# LightLink_V2.net
KiCad netlist of a schematic drawn in Altium Designer
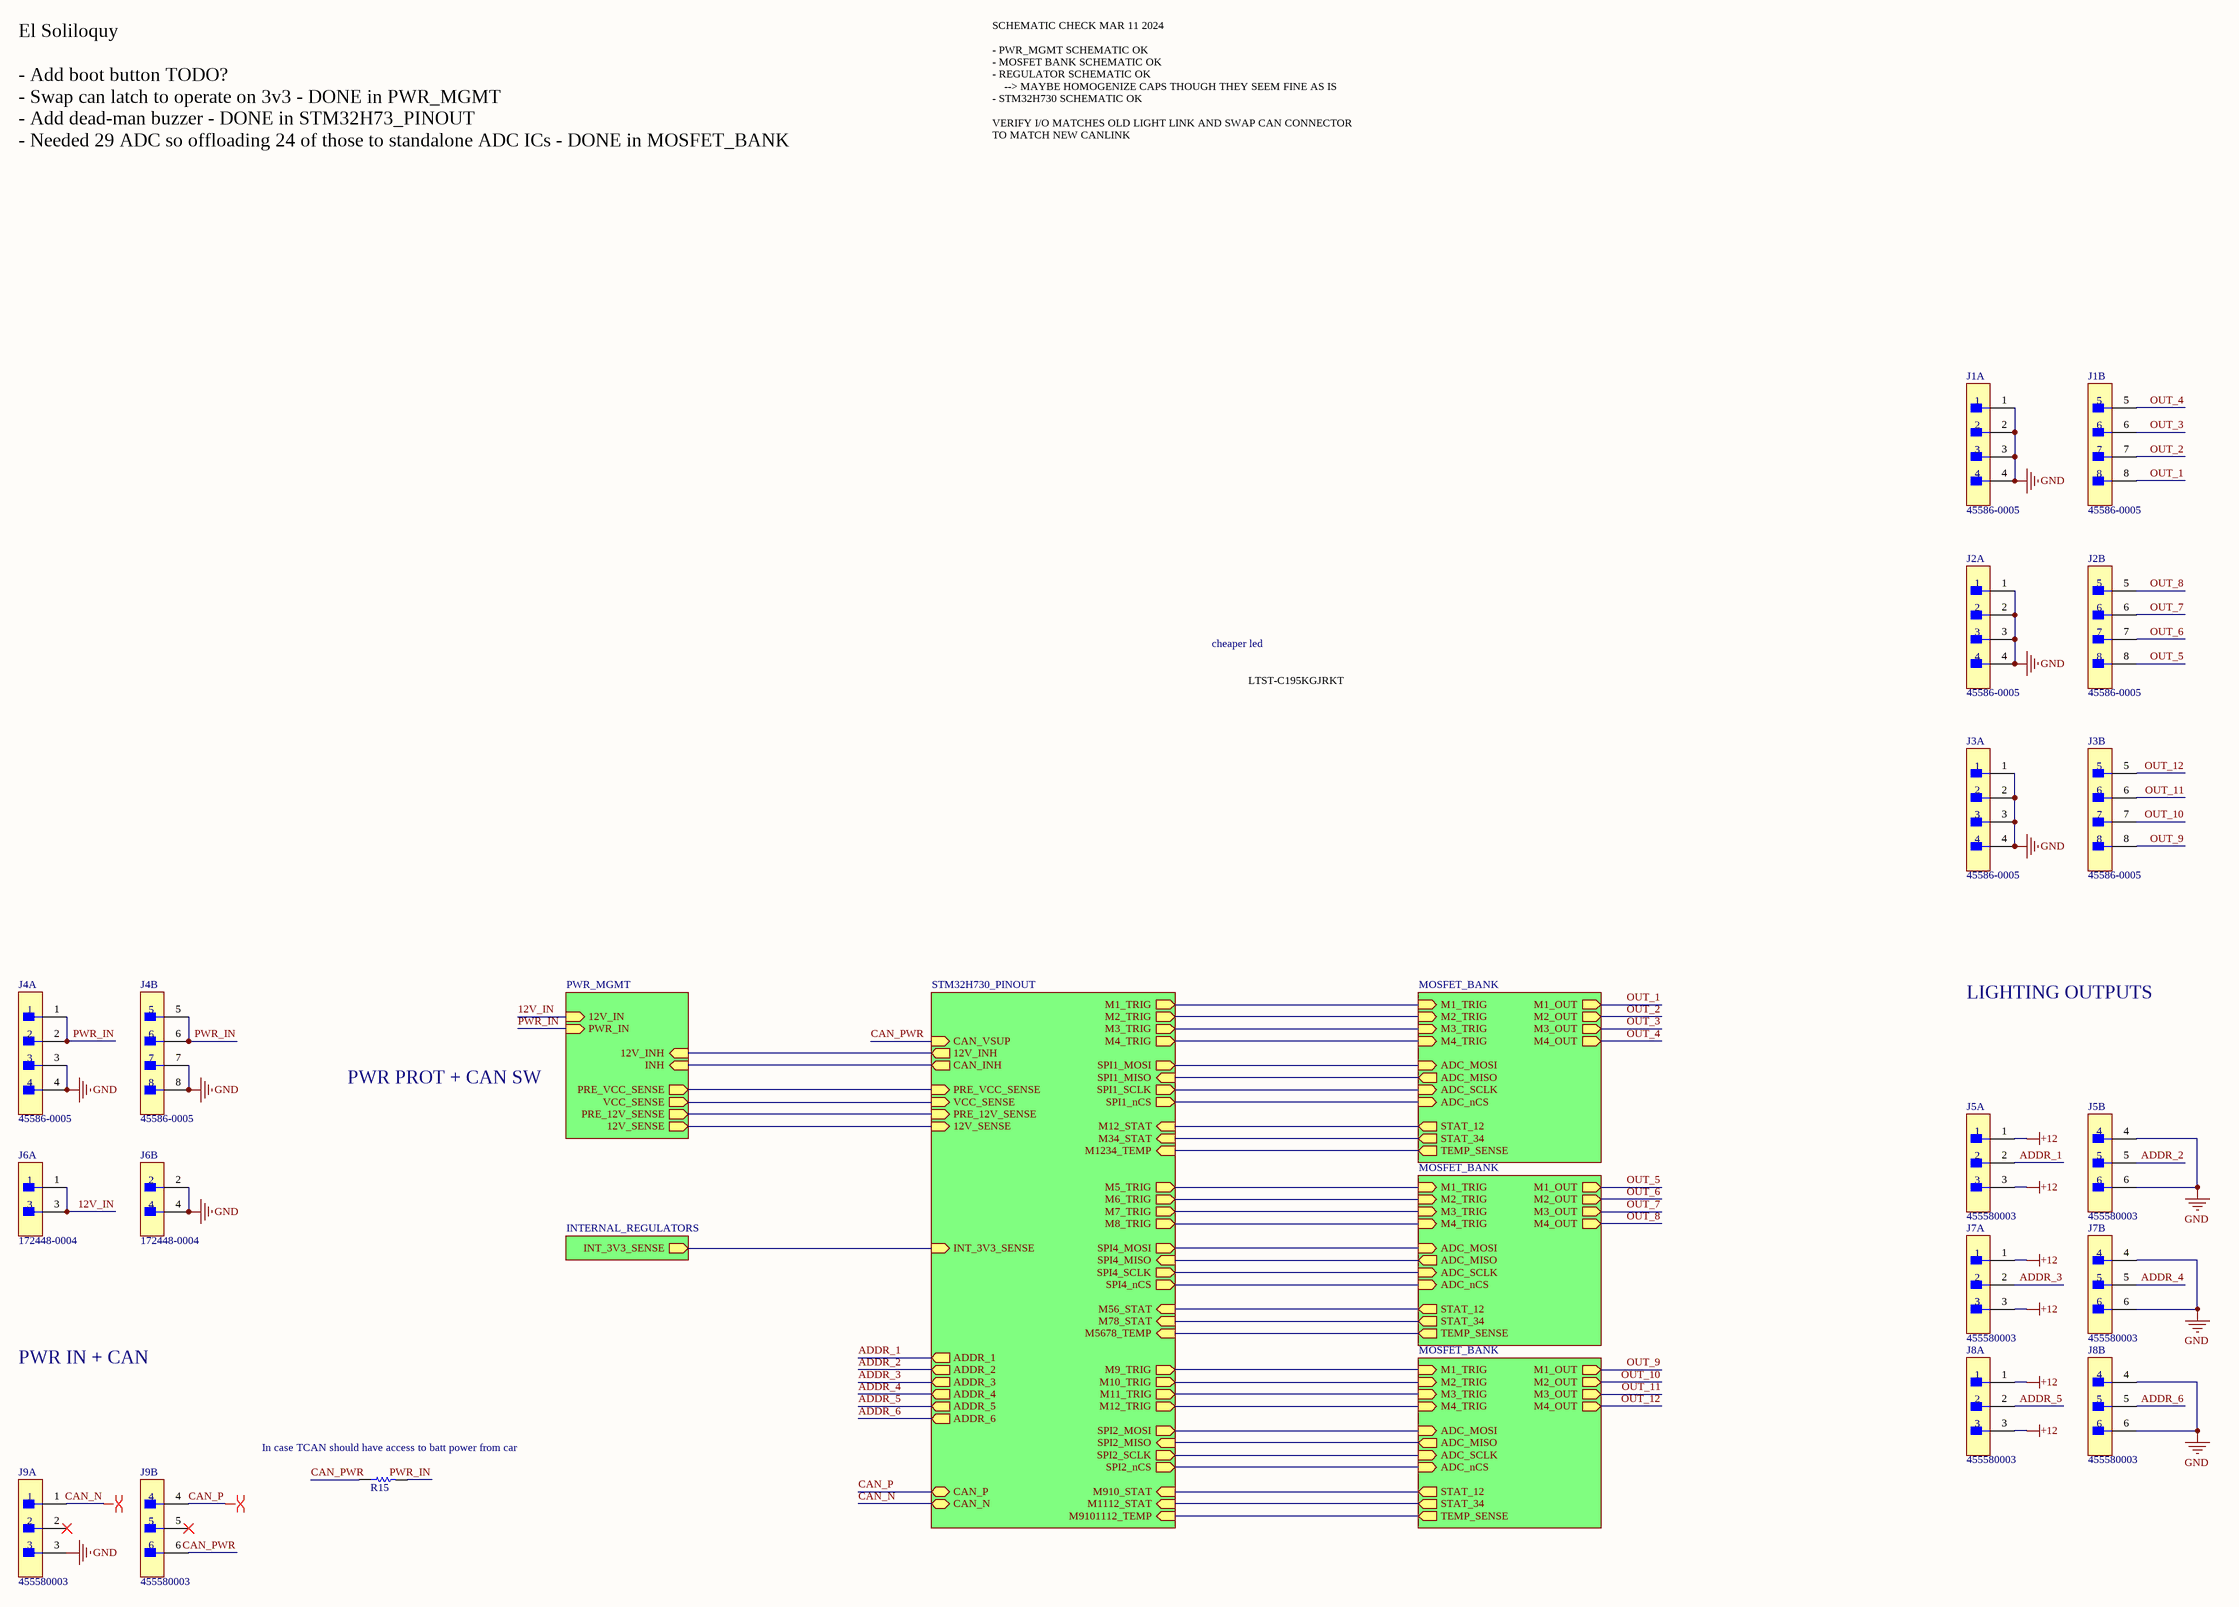
[diagram p0: LightLink_V2.SchDoc]

(export (version "E")
  (design (tool "Eeschema 10.0.6"))
  (components
    (comp (ref "J1")
      (value "45586-0005")
      (footprint "FP-45586-0005-MFG")
      (description "CONN HEADER R/A 8POS 4.2MM")
      (libsource (lib "Altium Content Vault") (part "85438c39ca9ef07d43bb2e97c52bc44"))
    )
    (comp (ref "J2")
      (value "45586-0005")
      (footprint "FP-45586-0005-MFG")
      (description "CONN HEADER R/A 8POS 4.2MM")
      (libsource (lib "Altium Content Vault") (part "85438c39ca9ef07d43bb2e97c52bc44"))
    )
    (comp (ref "J3")
      (value "45586-0005")
      (footprint "FP-45586-0005-MFG")
      (description "CONN HEADER R/A 8POS 4.2MM")
      (libsource (lib "Altium Content Vault") (part "85438c39ca9ef07d43bb2e97c52bc44"))
    )
    (comp (ref "J4")
      (value "45586-0005")
      (footprint "FP-45586-0005-MFG")
      (description "CONN HEADER R/A 8POS 4.2MM")
      (libsource (lib "Altium Content Vault") (part "85438c39ca9ef07d43bb2e97c52bc44"))
    )
    (comp (ref "J5")
      (value "455580003")
      (footprint "FP-455580003-MFG")
      (description "CONN HEADER R/A 6POS 4.2MM")
      (fields
        (field (name "OCTOPART") "https://octopart.com/45558-0003-molex-7672845")
        (field (name "MANUFACTURER") "Molex")
      )
      (libsource (lib "Altium Content Vault") (part "bb9cbdb24149a20ba329b4e86909569"))
    )
    (comp (ref "J6")
      (value "172448-0004")
      (footprint "FP-39-30-1041-MFG")
      (description "Different component but holes should line up. Original P/N is 39-30-1041")
      (fields
        (field (name "MANUFACTURER") "Molex")
        (field (name "OCTOPART") "https://octopart.com/39-30-1041-molex-276737")
      )
      (libsource (lib "Altium Content Vault") (part "1621473add15499e993d6bbd36d0f06"))
    )
    (comp (ref "J7")
      (value "455580003")
      (footprint "FP-455580003-MFG")
      (description "CONN HEADER R/A 6POS 4.2MM")
      (fields
        (field (name "OCTOPART") "https://octopart.com/45558-0003-molex-7672845")
        (field (name "MANUFACTURER") "Molex")
      )
      (libsource (lib "Altium Content Vault") (part "bb9cbdb24149a20ba329b4e86909569"))
    )
    (comp (ref "J8")
      (value "455580003")
      (footprint "FP-455580003-MFG")
      (description "CONN HEADER R/A 6POS 4.2MM")
      (fields
        (field (name "OCTOPART") "https://octopart.com/45558-0003-molex-7672845")
        (field (name "MANUFACTURER") "Molex")
      )
      (libsource (lib "Altium Content Vault") (part "bb9cbdb24149a20ba329b4e86909569"))
    )
    (comp (ref "J9")
      (value "455580003")
      (footprint "FP-455580003-MFG")
      (description "CONN HEADER R/A 6POS 4.2MM")
      (fields
        (field (name "OCTOPART") "https://octopart.com/45558-0003-molex-7672845")
        (field (name "MANUFACTURER") "Molex")
      )
      (libsource (lib "Altium Content Vault") (part "bb9cbdb24149a20ba329b4e86909569"))
    )
    (comp (ref "R15")
      (value "0603 JUMPER")
      (footprint "RESC1609X55X30ML15T15")
      (description "READ THE NAME")
      (libsource (lib "uORocketry Hardware") (part "RES-2"))
    )
  )
  (nets
    (net (code "1") (name "+12") (class "Default")
      (node (ref "J5") (pin "1") (pinfunction "1_1") (pintype "passive"))
      (node (ref "J5") (pin "3") (pinfunction "3_3") (pintype "passive"))
      (node (ref "J7") (pin "1") (pinfunction "1_1") (pintype "passive"))
      (node (ref "J7") (pin "3") (pinfunction "3_3") (pintype "passive"))
      (node (ref "J8") (pin "1") (pinfunction "1_1") (pintype "passive"))
      (node (ref "J8") (pin "3") (pinfunction "3_3") (pintype "passive"))
    )
    (net (code "2") (name "/12V_IN") (class "Default")
      (node (ref "J6") (pin "1") (pinfunction "1_1") (pintype "passive"))
      (node (ref "J6") (pin "3") (pinfunction "3_3") (pintype "passive"))
    )
    (net (code "8") (name "/ADDR_1") (class "Default")
      (node (ref "J5") (pin "2") (pinfunction "2_2") (pintype "passive"))
    )
    (net (code "9") (name "/ADDR_2") (class "Default")
      (node (ref "J5") (pin "5") (pinfunction "5_5") (pintype "passive"))
    )
    (net (code "10") (name "/ADDR_3") (class "Default")
      (node (ref "J7") (pin "2") (pinfunction "2_2") (pintype "passive"))
    )
    (net (code "11") (name "/ADDR_4") (class "Default")
      (node (ref "J7") (pin "5") (pinfunction "5_5") (pintype "passive"))
    )
    (net (code "12") (name "/ADDR_5") (class "Default")
      (node (ref "J8") (pin "2") (pinfunction "2_2") (pintype "passive"))
    )
    (net (code "13") (name "/ADDR_6") (class "Default")
      (node (ref "J8") (pin "5") (pinfunction "5_5") (pintype "passive"))
    )
    (net (code "15") (name "/CAN_N") (class "Default")
      (node (ref "J9") (pin "1") (pinfunction "1_1") (pintype "passive"))
    )
    (net (code "16") (name "/CAN_P") (class "Default")
      (node (ref "J9") (pin "4") (pinfunction "4_4") (pintype "passive"))
    )
    (net (code "17") (name "/CAN_PWR") (class "Default")
      (node (ref "J9") (pin "6") (pinfunction "6_6") (pintype "passive"))
      (node (ref "R15") (pin "1") (pinfunction "1_1") (pintype "passive"))
    )
    (net (code "31") (name "/OUT_1") (class "Default")
      (node (ref "J1") (pin "8") (pinfunction "8_8") (pintype "passive"))
    )
    (net (code "32") (name "/OUT_2") (class "Default")
      (node (ref "J1") (pin "7") (pinfunction "7_7") (pintype "passive"))
    )
    (net (code "33") (name "/OUT_3") (class "Default")
      (node (ref "J1") (pin "6") (pinfunction "6_6") (pintype "passive"))
    )
    (net (code "34") (name "/OUT_4") (class "Default")
      (node (ref "J1") (pin "5") (pinfunction "5_5") (pintype "passive"))
    )
    (net (code "35") (name "/OUT_5") (class "Default")
      (node (ref "J2") (pin "8") (pinfunction "8_8") (pintype "passive"))
    )
    (net (code "36") (name "/OUT_6") (class "Default")
      (node (ref "J2") (pin "7") (pinfunction "7_7") (pintype "passive"))
    )
    (net (code "37") (name "/OUT_7") (class "Default")
      (node (ref "J2") (pin "6") (pinfunction "6_6") (pintype "passive"))
    )
    (net (code "38") (name "/OUT_8") (class "Default")
      (node (ref "J2") (pin "5") (pinfunction "5_5") (pintype "passive"))
    )
    (net (code "39") (name "/OUT_9") (class "Default")
      (node (ref "J3") (pin "8") (pinfunction "8_8") (pintype "passive"))
    )
    (net (code "40") (name "/OUT_10") (class "Default")
      (node (ref "J3") (pin "7") (pinfunction "7_7") (pintype "passive"))
    )
    (net (code "41") (name "/OUT_11") (class "Default")
      (node (ref "J3") (pin "6") (pinfunction "6_6") (pintype "passive"))
    )
    (net (code "42") (name "/OUT_12") (class "Default")
      (node (ref "J3") (pin "5") (pinfunction "5_5") (pintype "passive"))
    )
    (net (code "45") (name "/PWR_IN") (class "Default")
      (node (ref "J4") (pin "1") (pinfunction "1_1") (pintype "passive"))
      (node (ref "J4") (pin "2") (pinfunction "2_2") (pintype "passive"))
      (node (ref "J4") (pin "5") (pinfunction "5_5") (pintype "passive"))
      (node (ref "J4") (pin "6") (pinfunction "6_6") (pintype "passive"))
      (node (ref "R15") (pin "2") (pinfunction "2_2") (pintype "passive"))
    )
    (net (code "65") (name "GND") (class "Default")
      (node (ref "J1") (pin "1") (pinfunction "1_1") (pintype "passive"))
      (node (ref "J1") (pin "2") (pinfunction "2_2") (pintype "passive"))
      (node (ref "J1") (pin "3") (pinfunction "3_3") (pintype "passive"))
      (node (ref "J1") (pin "4") (pinfunction "4_4") (pintype "passive"))
      (node (ref "J2") (pin "1") (pinfunction "1_1") (pintype "passive"))
      (node (ref "J2") (pin "2") (pinfunction "2_2") (pintype "passive"))
      (node (ref "J2") (pin "3") (pinfunction "3_3") (pintype "passive"))
      (node (ref "J2") (pin "4") (pinfunction "4_4") (pintype "passive"))
      (node (ref "J3") (pin "1") (pinfunction "1_1") (pintype "passive"))
      (node (ref "J3") (pin "2") (pinfunction "2_2") (pintype "passive"))
      (node (ref "J3") (pin "3") (pinfunction "3_3") (pintype "passive"))
      (node (ref "J3") (pin "4") (pinfunction "4_4") (pintype "passive"))
      (node (ref "J4") (pin "3") (pinfunction "3_3") (pintype "passive"))
      (node (ref "J4") (pin "4") (pinfunction "4_4") (pintype "passive"))
      (node (ref "J4") (pin "7") (pinfunction "7_7") (pintype "passive"))
      (node (ref "J4") (pin "8") (pinfunction "8_8") (pintype "passive"))
      (node (ref "J5") (pin "4") (pinfunction "4_4") (pintype "passive"))
      (node (ref "J5") (pin "6") (pinfunction "6_6") (pintype "passive"))
      (node (ref "J6") (pin "2") (pinfunction "2_2") (pintype "passive"))
      (node (ref "J6") (pin "4") (pinfunction "4_4") (pintype "passive"))
      (node (ref "J7") (pin "4") (pinfunction "4_4") (pintype "passive"))
      (node (ref "J7") (pin "6") (pinfunction "6_6") (pintype "passive"))
      (node (ref "J8") (pin "4") (pinfunction "4_4") (pintype "passive"))
      (node (ref "J8") (pin "6") (pinfunction "6_6") (pintype "passive"))
      (node (ref "J9") (pin "3") (pinfunction "3_3") (pintype "passive"))
    )
    (net (code "66") (name "unconnected-(J9-Pad2)") (class "Default")
      (node (ref "J9") (pin "2") (pinfunction "2_2") (pintype "passive+no_connect"))
    )
    (net (code "67") (name "unconnected-(J9-Pad5)") (class "Default")
      (node (ref "J9") (pin "5") (pinfunction "5_5") (pintype "passive+no_connect"))
    )
  )
)
